# fabflash-mk-2_2-booster.net
KiCad netlist of a schematic drawn in EAGLE
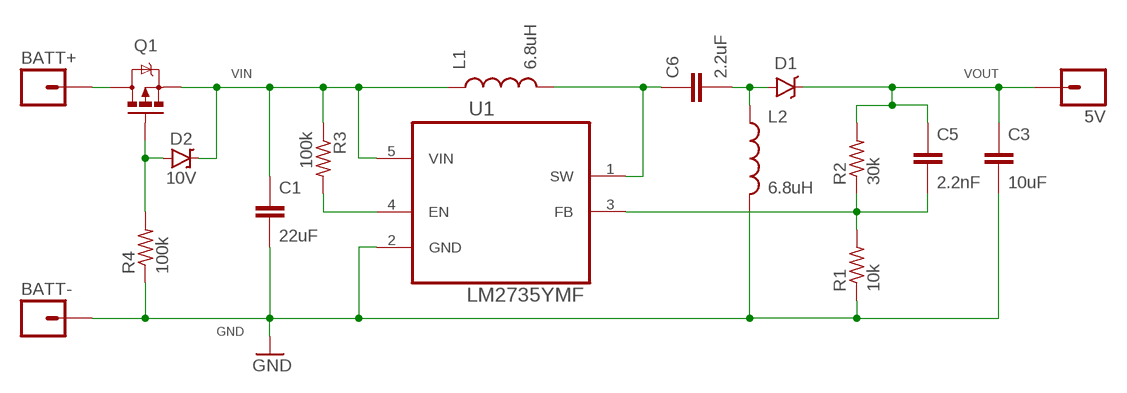
[diagram p0: schematic, sheet 1]

(export (version "E")
  (design (tool "Eeschema 10.0.6"))
  (components
    (comp (ref "5V")
      (value "M01PTH-1.2MM")
      (footprint "eagle-import:1X01-1.2MM")
      (libsource (lib "eagle-import") (part "M01PTH-1.2MM"))
    )
    (comp (ref "BATT+")
      (value "M01NOT-A-VIA-NOPE")
      (footprint "eagle-import:1X01_NOSILK_NOSTOP")
      (libsource (lib "eagle-import") (part "M01NOT-A-VIA-NOPE"))
    )
    (comp (ref "BATT-")
      (value "M01NOT-A-VIA-NOPE")
      (footprint "eagle-import:1X01_NOSILK_NOSTOP")
      (libsource (lib "eagle-import") (part "M01NOT-A-VIA-NOPE"))
    )
    (comp (ref "C1")
      (value "22uF")
      (footprint "eagle-import:C0805")
      (libsource (lib "eagle-import") (part "CAPACITOR-CERAMICC0805"))
    )
    (comp (ref "C3")
      (value "10uF")
      (footprint "eagle-import:C0805")
      (libsource (lib "eagle-import") (part "CAPACITOR-CERAMICC0805"))
    )
    (comp (ref "C5")
      (value "2.2nF")
      (footprint "eagle-import:C0603")
      (libsource (lib "eagle-import") (part "CAPACITOR-CERAMICC0603"))
    )
    (comp (ref "C6")
      (value "2.2uF")
      (footprint "eagle-import:C0805")
      (libsource (lib "eagle-import") (part "CAPACITOR-CERAMICC0805"))
    )
    (comp (ref "D1")
      (value "B340A")
      (footprint "eagle-import:SMA-DIODE")
      (libsource (lib "eagle-import") (part "DIODE-SCHOTTKYB340A"))
    )
    (comp (ref "D2")
      (value "10V")
      (footprint "eagle-import:SOD123")
      (libsource (lib "eagle-import") (part "DIODE-ZENERSOD123"))
    )
    (comp (ref "L1")
      (value "6.8uH")
      (footprint "eagle-import:TAIYO-YUDEN-40XX")
      (libsource (lib "eagle-import") (part "INDUCTORTAIYO-YUDEN-40XX"))
    )
    (comp (ref "L2")
      (value "6.8uH")
      (footprint "eagle-import:TAIYO-YUDEN-40XX")
      (libsource (lib "eagle-import") (part "INDUCTORTAIYO-YUDEN-40XX"))
    )
    (comp (ref "Q1")
      (value "MOSFET-PCHANNELIRLML2244")
      (footprint "eagle-import:SOT23-3")
      (libsource (lib "eagle-import") (part "MOSFET-PCHANNELIRLML2244"))
    )
    (comp (ref "R1")
      (value "10k")
      (footprint "eagle-import:R0603")
      (libsource (lib "eagle-import") (part "RESISTORR0603"))
    )
    (comp (ref "R2")
      (value "30k")
      (footprint "eagle-import:R0603")
      (libsource (lib "eagle-import") (part "RESISTORR0603"))
    )
    (comp (ref "R3")
      (value "100k")
      (footprint "eagle-import:R0603")
      (libsource (lib "eagle-import") (part "RESISTORR0603"))
    )
    (comp (ref "R4")
      (value "100k")
      (footprint "eagle-import:R0603")
      (libsource (lib "eagle-import") (part "RESISTORR0603"))
    )
    (comp (ref "U1")
      (value "LM2735YMF")
      (footprint "eagle-import:SOT95P285X110-5N")
      (libsource (lib "eagle-import") (part "LM2735YMF"))
    )
  )
  (nets
    (net (code "1") (name "/VIN") (class "Default")
      (node (ref "C1") (pin "1") (pinfunction "1_1") (pintype "passive"))
      (node (ref "D2") (pin "C") (pinfunction "C_C") (pintype "passive"))
      (node (ref "L1") (pin "1") (pinfunction "1_1") (pintype "passive"))
      (node (ref "Q1") (pin "2") (pinfunction "S_2") (pintype "passive"))
      (node (ref "R3") (pin "1") (pinfunction "1_1") (pintype "passive"))
      (node (ref "U1") (pin "5") (pinfunction "VIN_5") (pintype "power_in"))
    )
    (net (code "2") (name "/VOUT") (class "Default")
      (node (ref "5V") (pin "P$1") (pinfunction "1_P$1") (pintype "passive"))
      (node (ref "C3") (pin "1") (pinfunction "1_1") (pintype "passive"))
      (node (ref "C5") (pin "1") (pinfunction "1_1") (pintype "passive"))
      (node (ref "D1") (pin "C") (pinfunction "C_C") (pintype "passive"))
      (node (ref "R2") (pin "2") (pinfunction "2_2") (pintype "passive"))
    )
    (net (code "3") (name "GND") (class "Default")
      (node (ref "BATT-") (pin "P$1") (pinfunction "1_P$1") (pintype "passive"))
      (node (ref "C1") (pin "2") (pinfunction "2_2") (pintype "passive"))
      (node (ref "C3") (pin "2") (pinfunction "2_2") (pintype "passive"))
      (node (ref "L2") (pin "2") (pinfunction "2_2") (pintype "passive"))
      (node (ref "R1") (pin "1") (pinfunction "1_1") (pintype "passive"))
      (node (ref "R4") (pin "1") (pinfunction "1_1") (pintype "passive"))
      (node (ref "U1") (pin "2") (pinfunction "GND_2") (pintype "power_in"))
    )
    (net (code "4") (name "Net-(BATT+-1)") (class "Default")
      (node (ref "BATT+") (pin "P$1") (pinfunction "1_P$1") (pintype "passive"))
      (node (ref "Q1") (pin "3") (pinfunction "D_3") (pintype "passive"))
    )
    (net (code "5") (name "Net-(C6-Pad2)") (class "Default")
      (node (ref "C6") (pin "2") (pinfunction "2_2") (pintype "passive"))
      (node (ref "D1") (pin "A") (pinfunction "A_A") (pintype "passive"))
      (node (ref "L2") (pin "1") (pinfunction "1_1") (pintype "passive"))
    )
    (net (code "6") (name "Net-(Q1-G)") (class "Default")
      (node (ref "D2") (pin "A") (pinfunction "A_A") (pintype "passive"))
      (node (ref "Q1") (pin "1") (pinfunction "G_1") (pintype "passive"))
      (node (ref "R4") (pin "2") (pinfunction "2_2") (pintype "passive"))
    )
    (net (code "7") (name "Net-(U1-EN)") (class "Default")
      (node (ref "R3") (pin "2") (pinfunction "2_2") (pintype "passive"))
      (node (ref "U1") (pin "4") (pinfunction "EN_4") (pintype "input"))
    )
    (net (code "8") (name "Net-(U1-FB)") (class "Default")
      (node (ref "C5") (pin "2") (pinfunction "2_2") (pintype "passive"))
      (node (ref "R1") (pin "2") (pinfunction "2_2") (pintype "passive"))
      (node (ref "R2") (pin "1") (pinfunction "1_1") (pintype "passive"))
      (node (ref "U1") (pin "3") (pinfunction "FB_3") (pintype "input"))
    )
    (net (code "9") (name "Net-(U1-SW)") (class "Default")
      (node (ref "C6") (pin "1") (pinfunction "1_1") (pintype "passive"))
      (node (ref "L1") (pin "2") (pinfunction "2_2") (pintype "passive"))
      (node (ref "U1") (pin "1") (pinfunction "SW_1") (pintype "power_in"))
    )
  )
)
